# H.net
KiCad netlist of a schematic drawn in Altium Designer
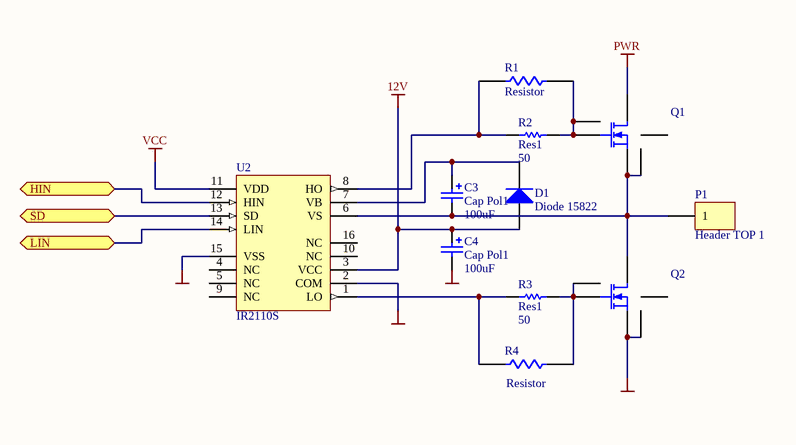
[diagram p0: H.SchDoc]

(export (version "E")
  (design (tool "Eeschema 10.0.6"))
  (components
    (comp (ref "C3")
      (value "Cap Pol1")
      (footprint "CAPR-Small")
      (description "Polarized Capacitor (Radial)")
      (fields (field (name "ALTIUM_VALUE") "100uF") (field (name "PUBLISHER") "Altium Limited"))
      (libsource (lib "Project") (part "Cap Pol1"))
    )
    (comp (ref "C4")
      (value "Cap Pol1")
      (footprint "CAPR-Small")
      (description "Polarized Capacitor (Radial)")
      (fields (field (name "ALTIUM_VALUE") "100uF") (field (name "PUBLISHER") "Altium Limited"))
      (libsource (lib "Project") (part "Cap Pol1"))
    )
    (comp (ref "D1")
      (value "Diode 15822")
      (footprint "DO-35")
      (description "High Conductance Fast Diode")
      (fields (field (name "PUBLISHER") "Altium Limited"))
      (libsource (lib "Miscellaneous Devices") (part "Diode 1N4448"))
    )
    (comp (ref "P1")
      (value "Header TOP 1")
      (footprint "PIN1")
      (description "Header, 1Pin")
      (fields (field (name "PUBLISHER") "Altium Limited"))
      (libsource (lib "Project") (part "Header TOP 1"))
    )
    (comp (ref "Q1")
      (value "NMOSFET-UNIVERSAL")
      (footprint "NMOSFET-UNIVERSAL")
      (description "N-Channel MOSFET")
      (fields (field (name "PUBLISHER") "Altium Limited"))
      (libsource (lib "Project") (part "NMOSFET-UNIVERSAL"))
    )
    (comp (ref "Q2")
      (value "NMOSFET-UNIVERSAL")
      (footprint "NMOSFET-UNIVERSAL")
      (description "N-Channel MOSFET")
      (fields (field (name "PUBLISHER") "Altium Limited"))
      (libsource (lib "Project") (part "NMOSFET-UNIVERSAL"))
    )
    (comp (ref "R1")
      (value "Resistor")
      (footprint "6-0805_M")
      (fields (field (name "PUBLISHER") "Altium Limited"))
      (libsource (lib "Project") (part "Resistor"))
    )
    (comp (ref "R2")
      (value "Res1")
      (footprint "AXIAL-0.3")
      (description "Resistor")
      (fields (field (name "ALTIUM_VALUE") "50") (field (name "PUBLISHER") "Altium Limited"))
      (libsource (lib "Miscellaneous Devices") (part "Res1"))
    )
    (comp (ref "R3")
      (value "Res1")
      (footprint "AXIAL-0.3")
      (description "Resistor")
      (fields (field (name "ALTIUM_VALUE") "50") (field (name "PUBLISHER") "Altium Limited"))
      (libsource (lib "Miscellaneous Devices") (part "Res1"))
    )
    (comp (ref "R4")
      (value "Resistor")
      (footprint "6-0805_M")
      (fields (field (name "PUBLISHER") "Altium Limited"))
      (libsource (lib "Project") (part "Resistor"))
    )
    (comp (ref "U2")
      (value "IR2110S")
      (footprint "International Rectifier Footprints:SOIC16_N")
      (description "High and Low Side Driver")
      (fields (field (name "PUBLISHER") "Altium Limited"))
      (libsource (lib "IR Interface Bridge Driver") (part "IR2110S"))
    )
  )
  (nets
    (net (code "1") (name "/HIN") (class "Default")
      (node (ref "U2") (pin "12") (pinfunction "HIN_12") (pintype "input"))
    )
    (net (code "2") (name "/LIN") (class "Default")
      (node (ref "U2") (pin "14") (pinfunction "LIN_14") (pintype "input"))
    )
    (net (code "3") (name "/SD") (class "Default")
      (node (ref "U2") (pin "13") (pinfunction "SD_13") (pintype "input"))
    )
    (net (code "4") (name "12V") (class "Default")
      (node (ref "C4") (pin "1") (pinfunction "1_1") (pintype "passive"))
      (node (ref "D1") (pin "1") (pinfunction "A_1") (pintype "passive"))
      (node (ref "U2") (pin "3") (pinfunction "VCC_3") (pintype "power_in"))
    )
    (net (code "5") (name "GND") (class "Default")
      (node (ref "C4") (pin "2") (pinfunction "2_2") (pintype "passive"))
      (node (ref "Q2") (pin "3") (pinfunction "S_3") (pintype "passive"))
      (node (ref "Q2") (pin "5") (pintype "passive"))
      (node (ref "U2") (pin "15") (pinfunction "VSS_15") (pintype "power_in"))
      (node (ref "U2") (pin "2") (pinfunction "COM_2") (pintype "power_in"))
    )
    (net (code "6") (name "Net-(D1-K)") (class "Default")
      (node (ref "C3") (pin "1") (pinfunction "1_1") (pintype "passive"))
      (node (ref "D1") (pin "2") (pinfunction "K_2") (pintype "passive"))
      (node (ref "U2") (pin "7") (pinfunction "VB_7") (pintype "power_in"))
    )
    (net (code "7") (name "Net-(Q1-G)") (class "Default")
      (node (ref "Q1") (pin "1") (pinfunction "G_1") (pintype "passive"))
      (node (ref "Q1") (pin "4") (pintype "passive"))
      (node (ref "R1") (pin "1") (pinfunction "1_1") (pintype "passive"))
      (node (ref "R2") (pin "2") (pinfunction "2_2") (pintype "passive"))
    )
    (net (code "8") (name "Net-(Q1-S)") (class "Default")
      (node (ref "C3") (pin "2") (pinfunction "2_2") (pintype "passive"))
      (node (ref "P1") (pin "1") (pinfunction "1_1") (pintype "passive"))
      (node (ref "Q1") (pin "3") (pinfunction "S_3") (pintype "passive"))
      (node (ref "Q1") (pin "5") (pintype "passive"))
      (node (ref "Q2") (pin "2") (pinfunction "D_2") (pintype "passive"))
      (node (ref "U2") (pin "6") (pinfunction "VS_6") (pintype "power_in"))
    )
    (net (code "9") (name "Net-(Q2-G)") (class "Default")
      (node (ref "Q2") (pin "1") (pinfunction "G_1") (pintype "passive"))
      (node (ref "Q2") (pin "4") (pintype "passive"))
      (node (ref "R3") (pin "2") (pinfunction "2_2") (pintype "passive"))
      (node (ref "R4") (pin "1") (pinfunction "1_1") (pintype "passive"))
    )
    (net (code "10") (name "Net-(U2-HO)") (class "Default")
      (node (ref "R1") (pin "2") (pinfunction "2_2") (pintype "passive"))
      (node (ref "R2") (pin "1") (pinfunction "1_1") (pintype "passive"))
      (node (ref "U2") (pin "8") (pinfunction "HO_8") (pintype "output"))
    )
    (net (code "11") (name "Net-(U2-LO)") (class "Default")
      (node (ref "R3") (pin "1") (pinfunction "1_1") (pintype "passive"))
      (node (ref "R4") (pin "2") (pinfunction "2_2") (pintype "passive"))
      (node (ref "U2") (pin "1") (pinfunction "LO_1") (pintype "output"))
    )
    (net (code "12") (name "PWR") (class "Default")
      (node (ref "Q1") (pin "2") (pinfunction "D_2") (pintype "passive"))
    )
    (net (code "13") (name "VCC") (class "Default")
      (node (ref "U2") (pin "11") (pinfunction "VDD_11") (pintype "power_in"))
    )
    (net (code "14") (name "unconnected-(Q1-Pad6)") (class "Default")
      (node (ref "Q1") (pin "6") (pintype "passive"))
    )
    (net (code "15") (name "unconnected-(Q2-Pad6)") (class "Default")
      (node (ref "Q2") (pin "6") (pintype "passive"))
    )
    (net (code "16") (name "unconnected-(U2-NC-Pad4)") (class "Default")
      (node (ref "U2") (pin "4") (pinfunction "NC_4") (pintype "passive"))
    )
    (net (code "17") (name "unconnected-(U2-NC-Pad5)") (class "Default")
      (node (ref "U2") (pin "5") (pinfunction "NC_5") (pintype "passive"))
    )
    (net (code "18") (name "unconnected-(U2-NC-Pad9)") (class "Default")
      (node (ref "U2") (pin "9") (pinfunction "NC_9") (pintype "passive"))
    )
    (net (code "19") (name "unconnected-(U2-NC-Pad10)") (class "Default")
      (node (ref "U2") (pin "10") (pinfunction "NC_10") (pintype "passive"))
    )
    (net (code "20") (name "unconnected-(U2-NC-Pad16)") (class "Default")
      (node (ref "U2") (pin "16") (pinfunction "NC_16") (pintype "passive"))
    )
  )
)
